# Voorvork.net
KiCad netlist of a schematic drawn in Altium Designer
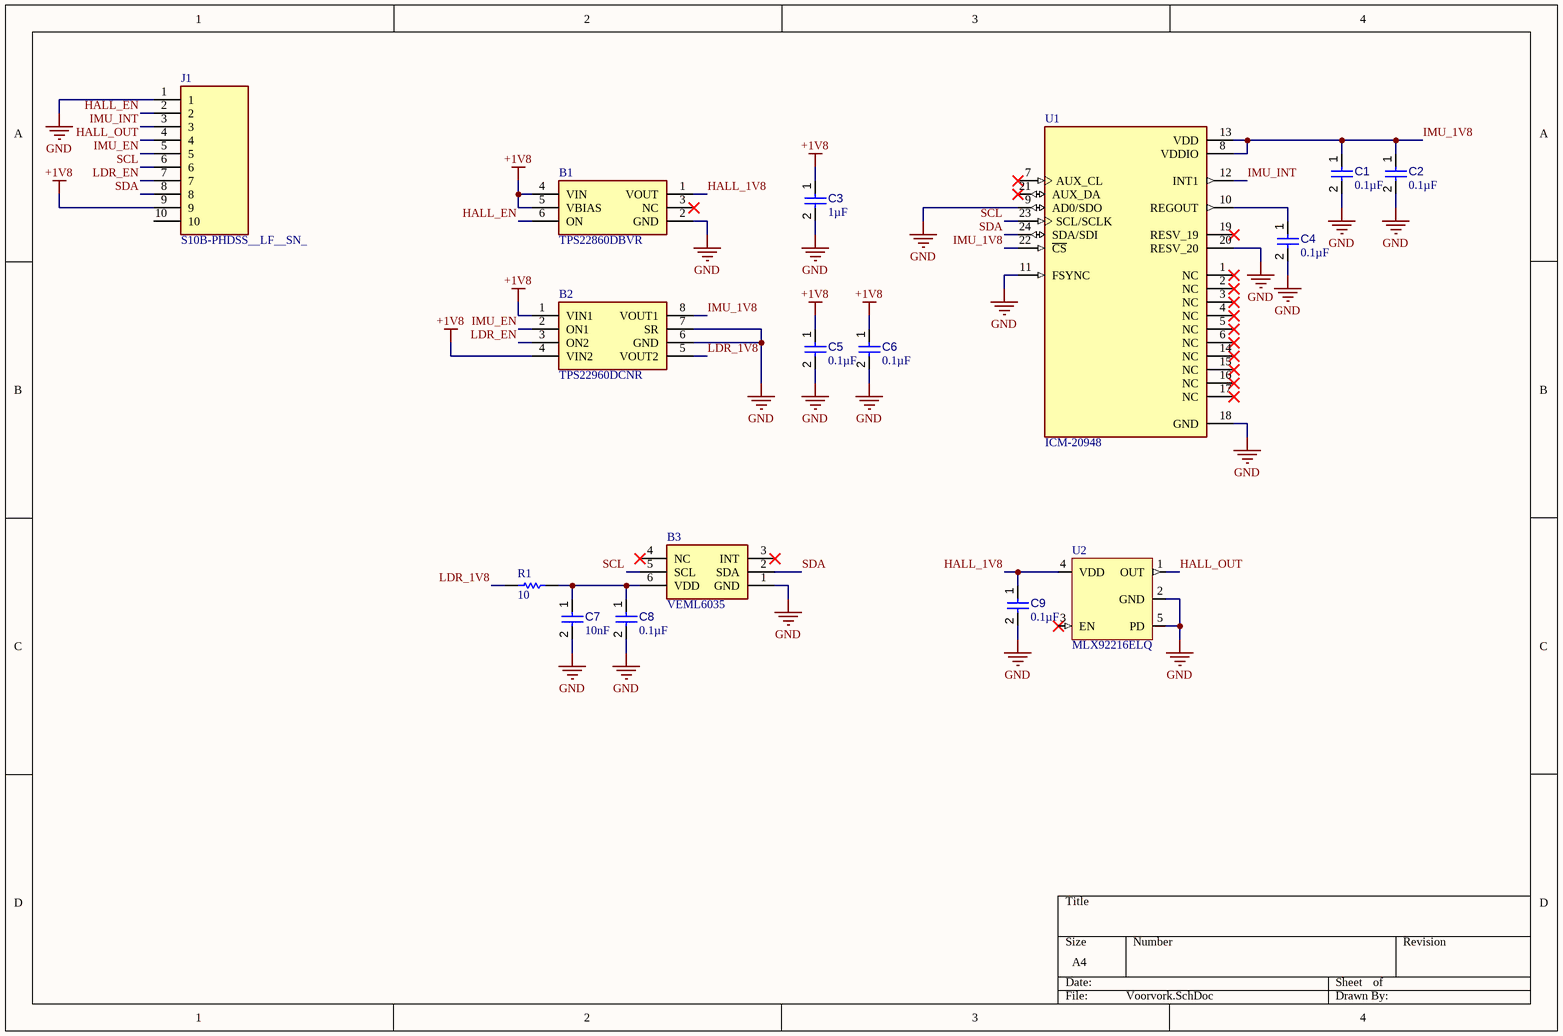
[diagram p0: Voorvork.SchDoc]

(export (version "E")
  (design (tool "Eeschema 10.0.6"))
  (components
    (comp (ref "B1")
      (value "TPS22860DBVR")
      (footprint "SOT95P280X145-6N")
      (description "TPS22860 Ultra-low leakage load switch")
      (fields (field (name "MOUSER PART NUMBER") "595-TPS22860DBVR"))
      (libsource (lib "Integrated_Library1") (part "TPS22860DBVR"))
    )
    (comp (ref "B2")
      (value "TPS22960DCNR")
      (footprint "SOP65P280X145-8N")
      (description "5.5-V, 0.5-A, 435m, 2-channel load switch with quick output discharge")
      (fields (field (name "MOUSER PART NUMBER") "595-TPS22960DCNR"))
      (libsource (lib "Integrated_Library1") (part "TPS22960DCNR"))
    )
    (comp (ref "B3")
      (value "VEML6035")
      (footprint "VEML6035")
      (description "VISHAY - VEML6035 - AMBIENT LIGHT PHOTO SENSOR, I2C, SMD-6")
      (fields (field (name "MOUSER PART NUMBER") "78-VEML6035"))
      (libsource (lib "Integrated_Library1") (part "VEML6035"))
    )
    (comp (ref "C1")
      (value "0.1µF")
      (footprint "CAPC2013X95X50LL10T25")
      (description "Chip Capacitor, 100 nF, +/- 10%, 50 V, 0805 (2012 Metric)")
      (fields (field (name "TOLERANCE") "10%") (field (name "Comment") "Capacitor 100 nF +/-10% 50 V 0805"))
      (libsource (lib "Arne Van der Stede") (part "CAP-NP-2"))
    )
    (comp (ref "C2")
      (value "0.1µF")
      (footprint "CAPC2013X95X50LL10T25")
      (description "Chip Capacitor, 100 nF, +/- 10%, 50 V, 0805 (2012 Metric)")
      (fields (field (name "TOLERANCE") "10%") (field (name "Comment") "Capacitor 100 nF +/-10% 50 V 0805"))
      (libsource (lib "Arne Van der Stede") (part "CAP-NP-2"))
    )
    (comp (ref "C3")
      (value "1µF")
      (footprint "CAPC2013X95X50LL10T25")
      (description "Chip Capacitor, 100 nF, +/- 10%, 50 V, 0805 (2012 Metric)")
      (fields (field (name "TOLERANCE") "10%") (field (name "Comment") "Capacitor 100 nF +/-10% 50 V 0805"))
      (libsource (lib "Arne Van der Stede") (part "CAP-NP-2"))
    )
    (comp (ref "C4")
      (value "0.1µF")
      (footprint "CAPC2013X95X50LL10T25")
      (description "Chip Capacitor, 100 nF, +/- 10%, 50 V, 0805 (2012 Metric)")
      (fields (field (name "TOLERANCE") "10%") (field (name "Comment") "Capacitor 100 nF +/-10% 50 V 0805"))
      (libsource (lib "Arne Van der Stede") (part "CAP-NP-2"))
    )
    (comp (ref "C5")
      (value "0.1µF")
      (footprint "CAPC2013X95X50LL10T25")
      (description "Chip Capacitor, 100 nF, +/- 10%, 50 V, 0805 (2012 Metric)")
      (fields (field (name "TOLERANCE") "10%") (field (name "Comment") "Capacitor 100 nF +/-10% 50 V 0805"))
      (libsource (lib "Arne Van der Stede") (part "CAP-NP-2"))
    )
    (comp (ref "C6")
      (value "0.1µF")
      (footprint "CAPC2013X95X50LL10T25")
      (description "Chip Capacitor, 100 nF, +/- 10%, 50 V, 0805 (2012 Metric)")
      (fields (field (name "TOLERANCE") "10%") (field (name "Comment") "Capacitor 100 nF +/-10% 50 V 0805"))
      (libsource (lib "Arne Van der Stede") (part "CAP-NP-2"))
    )
    (comp (ref "C7")
      (value "10nF")
      (footprint "CAPC2013X95X50LL10T25")
      (description "Chip Capacitor, 100 nF, +/- 10%, 50 V, 0805 (2012 Metric)")
      (fields (field (name "TOLERANCE") "10%") (field (name "Comment") "Capacitor 100 nF +/-10% 50 V 0805"))
      (libsource (lib "Arne Van der Stede") (part "CAP-NP-2"))
    )
    (comp (ref "C8")
      (value "0.1µF")
      (footprint "CAPC2013X95X50LL10T25")
      (description "Chip Capacitor, 100 nF, +/- 10%, 50 V, 0805 (2012 Metric)")
      (fields (field (name "TOLERANCE") "10%") (field (name "Comment") "Capacitor 100 nF +/-10% 50 V 0805"))
      (libsource (lib "Arne Van der Stede") (part "CAP-NP-2"))
    )
    (comp (ref "C9")
      (value "0.1µF")
      (footprint "CAPC2013X95X50LL10T25")
      (description "Chip Capacitor, 100 nF, +/- 10%, 50 V, 0805 (2012 Metric)")
      (fields (field (name "TOLERANCE") "10%") (field (name "Comment") "Capacitor 100 nF +/-10% 50 V 0805"))
      (libsource (lib "Arne Van der Stede") (part "CAP-NP-2"))
    )
    (comp (ref "J1")
      (value "S10B-PHDSS__LF__SN_")
      (footprint "S10BPHDSSLFSN")
      (description "Connector Header Through Hole, Right Angle 10 position 0.079\" (2.00mm)")
      (fields (field (name "MANUFACTURER_PART_NUMBER") "S10B-PHDSS (LF)(SN)"))
      (libsource (lib "Integrated_Library1") (part "S10B-PHDSS__LF__SN_"))
    )
    (comp (ref "R1")
      (value "10")
      (footprint "RESC2013X70X40ML20T20")
      (description "Chip Resistor, 1 KOhm, +/- 1%, 0.125 W, -55 to 155 degC, 0805 (2013 Metric)")
      (fields (field (name "TOLERANCE") "1%") (field (name "POWER") "125mW"))
      (libsource (lib "Arne Van der Stede") (part "RES-2"))
    )
    (comp (ref "U1")
      (value "ICM-20948")
      (footprint "QFN40P300X300X105-24N")
      (description "Accelerometer, Gyroscope, Magnetometer, 9 Axis Sensor I2C, SPI Output")
      (fields (field (name "MF") "TDK InvenSense"))
      (libsource (lib "Arne Van der Stede") (part "ICM-20948"))
    )
    (comp (ref "U2")
      (value "MLX92216ELQ")
      (footprint "DFN-4L")
      (libsource (lib "Integrated_Library1") (part "MLX92216ELQ"))
    )
  )
  (nets
    (net (code "1") (name "+1V8") (class "Default")
      (node (ref "B1") (pin "4") (pinfunction "VIN_4") (pintype "passive"))
      (node (ref "B1") (pin "5") (pinfunction "VBIAS_5") (pintype "passive"))
      (node (ref "B2") (pin "1") (pinfunction "VIN1_1") (pintype "passive"))
      (node (ref "B2") (pin "4") (pinfunction "VIN2_4") (pintype "passive"))
      (node (ref "C3") (pin "1") (pinfunction "1_1") (pintype "passive"))
      (node (ref "C5") (pin "1") (pinfunction "1_1") (pintype "passive"))
      (node (ref "C6") (pin "1") (pinfunction "1_1") (pintype "passive"))
      (node (ref "J1") (pin "9") (pinfunction "9_9") (pintype "passive"))
    )
    (net (code "2") (name "/HALL_1V8") (class "Default")
      (node (ref "B1") (pin "1") (pinfunction "VOUT_1") (pintype "passive"))
      (node (ref "C9") (pin "1") (pinfunction "1_1") (pintype "passive"))
      (node (ref "U2") (pin "4") (pinfunction "VDD_4") (pintype "power_in"))
    )
    (net (code "3") (name "/HALL_EN") (class "Default")
      (node (ref "B1") (pin "6") (pinfunction "ON_6") (pintype "passive"))
      (node (ref "J1") (pin "2") (pinfunction "2_2") (pintype "passive"))
    )
    (net (code "4") (name "/HALL_OUT") (class "Default")
      (node (ref "J1") (pin "4") (pinfunction "4_4") (pintype "passive"))
      (node (ref "U2") (pin "1") (pinfunction "OUT_1") (pintype "output"))
    )
    (net (code "5") (name "/IMU_1V8") (class "Default")
      (node (ref "B2") (pin "8") (pinfunction "VOUT1_8") (pintype "passive"))
      (node (ref "C1") (pin "1") (pinfunction "1_1") (pintype "passive"))
      (node (ref "C2") (pin "1") (pinfunction "1_1") (pintype "passive"))
      (node (ref "U1") (pin "13") (pinfunction "VDD_13") (pintype "power_in"))
      (node (ref "U1") (pin "22") (pinfunction "~{CS}_22") (pintype "input"))
      (node (ref "U1") (pin "8") (pinfunction "VDDIO_8") (pintype "power_in"))
    )
    (net (code "6") (name "/IMU_EN") (class "Default")
      (node (ref "B2") (pin "2") (pinfunction "ON1_2") (pintype "passive"))
      (node (ref "J1") (pin "5") (pinfunction "5_5") (pintype "passive"))
    )
    (net (code "7") (name "/IMU_INT") (class "Default")
      (node (ref "J1") (pin "3") (pinfunction "3_3") (pintype "passive"))
      (node (ref "U1") (pin "12") (pinfunction "INT1_12") (pintype "output"))
    )
    (net (code "8") (name "/LDR_1V8") (class "Default")
      (node (ref "B2") (pin "5") (pinfunction "VOUT2_5") (pintype "passive"))
      (node (ref "R1") (pin "1") (pinfunction "1_1") (pintype "passive"))
    )
    (net (code "9") (name "/LDR_EN") (class "Default")
      (node (ref "B2") (pin "3") (pinfunction "ON2_3") (pintype "passive"))
      (node (ref "J1") (pin "7") (pinfunction "7_7") (pintype "passive"))
    )
    (net (code "10") (name "/SCL") (class "Default")
      (node (ref "B3") (pin "5") (pinfunction "SCL_5") (pintype "passive"))
      (node (ref "J1") (pin "6") (pinfunction "6_6") (pintype "passive"))
      (node (ref "U1") (pin "23") (pinfunction "SCL/SCLK_23") (pintype "input"))
    )
    (net (code "11") (name "/SDA") (class "Default")
      (node (ref "B3") (pin "2") (pinfunction "SDA_2") (pintype "passive"))
      (node (ref "J1") (pin "8") (pinfunction "8_8") (pintype "passive"))
      (node (ref "U1") (pin "24") (pinfunction "SDA/SDI_24") (pintype "bidirectional"))
    )
    (net (code "12") (name "GND") (class "Default")
      (node (ref "B1") (pin "2") (pinfunction "GND_2") (pintype "passive"))
      (node (ref "B2") (pin "6") (pinfunction "GND_6") (pintype "passive"))
      (node (ref "B2") (pin "7") (pinfunction "SR_7") (pintype "passive"))
      (node (ref "B3") (pin "1") (pinfunction "GND_1") (pintype "passive"))
      (node (ref "C1") (pin "2") (pinfunction "2_2") (pintype "passive"))
      (node (ref "C2") (pin "2") (pinfunction "2_2") (pintype "passive"))
      (node (ref "C3") (pin "2") (pinfunction "2_2") (pintype "passive"))
      (node (ref "C4") (pin "2") (pinfunction "2_2") (pintype "passive"))
      (node (ref "C5") (pin "2") (pinfunction "2_2") (pintype "passive"))
      (node (ref "C6") (pin "2") (pinfunction "2_2") (pintype "passive"))
      (node (ref "C7") (pin "2") (pinfunction "2_2") (pintype "passive"))
      (node (ref "C8") (pin "2") (pinfunction "2_2") (pintype "passive"))
      (node (ref "C9") (pin "2") (pinfunction "2_2") (pintype "passive"))
      (node (ref "J1") (pin "1") (pinfunction "1_1") (pintype "passive"))
      (node (ref "U1") (pin "11") (pinfunction "FSYNC_11") (pintype "input"))
      (node (ref "U1") (pin "18") (pinfunction "GND_18") (pintype "power_in"))
      (node (ref "U1") (pin "20") (pinfunction "RESV_20_20") (pintype "passive"))
      (node (ref "U1") (pin "9") (pinfunction "AD0/SDO_9") (pintype "bidirectional"))
      (node (ref "U2") (pin "2") (pinfunction "GND_2") (pintype "passive"))
      (node (ref "U2") (pin "5") (pinfunction "PD_5") (pintype "passive"))
    )
    (net (code "13") (name "Net-(B3-VDD)") (class "Default")
      (node (ref "B3") (pin "6") (pinfunction "VDD_6") (pintype "passive"))
      (node (ref "C7") (pin "1") (pinfunction "1_1") (pintype "passive"))
      (node (ref "C8") (pin "1") (pinfunction "1_1") (pintype "passive"))
      (node (ref "R1") (pin "2") (pinfunction "2_2") (pintype "passive"))
    )
    (net (code "14") (name "Net-(U1-REGOUT)") (class "Default")
      (node (ref "C4") (pin "1") (pinfunction "1_1") (pintype "passive"))
      (node (ref "U1") (pin "10") (pinfunction "REGOUT_10") (pintype "output"))
    )
    (net (code "15") (name "unconnected-(B1-NC-Pad3)") (class "Default")
      (node (ref "B1") (pin "3") (pinfunction "NC_3") (pintype "passive+no_connect"))
    )
    (net (code "16") (name "unconnected-(B3-INT-Pad3)") (class "Default")
      (node (ref "B3") (pin "3") (pinfunction "INT_3") (pintype "passive+no_connect"))
    )
    (net (code "17") (name "unconnected-(B3-NC-Pad4)") (class "Default")
      (node (ref "B3") (pin "4") (pinfunction "NC_4") (pintype "passive+no_connect"))
    )
    (net (code "18") (name "unconnected-(J1-Pad10)") (class "Default")
      (node (ref "J1") (pin "10") (pinfunction "10_10") (pintype "passive"))
    )
    (net (code "19") (name "unconnected-(U1-AUX_CL-Pad7)") (class "Default")
      (node (ref "U1") (pin "7") (pinfunction "AUX_CL_7") (pintype "input+no_connect"))
    )
    (net (code "20") (name "unconnected-(U1-AUX_DA-Pad21)") (class "Default")
      (node (ref "U1") (pin "21") (pinfunction "AUX_DA_21") (pintype "bidirectional+no_connect"))
    )
    (net (code "21") (name "unconnected-(U1-NC-Pad1)") (class "Default")
      (node (ref "U1") (pin "1") (pinfunction "NC_1") (pintype "passive+no_connect"))
    )
    (net (code "22") (name "unconnected-(U1-NC-Pad2)") (class "Default")
      (node (ref "U1") (pin "2") (pinfunction "NC_2") (pintype "passive+no_connect"))
    )
    (net (code "23") (name "unconnected-(U1-NC-Pad3)") (class "Default")
      (node (ref "U1") (pin "3") (pinfunction "NC_3") (pintype "passive+no_connect"))
    )
    (net (code "24") (name "unconnected-(U1-NC-Pad4)") (class "Default")
      (node (ref "U1") (pin "4") (pinfunction "NC_4") (pintype "passive+no_connect"))
    )
    (net (code "25") (name "unconnected-(U1-NC-Pad5)") (class "Default")
      (node (ref "U1") (pin "5") (pinfunction "NC_5") (pintype "passive+no_connect"))
    )
    (net (code "26") (name "unconnected-(U1-NC-Pad6)") (class "Default")
      (node (ref "U1") (pin "6") (pinfunction "NC_6") (pintype "passive+no_connect"))
    )
    (net (code "27") (name "unconnected-(U1-NC-Pad14)") (class "Default")
      (node (ref "U1") (pin "14") (pinfunction "NC_14") (pintype "passive+no_connect"))
    )
    (net (code "28") (name "unconnected-(U1-NC-Pad15)") (class "Default")
      (node (ref "U1") (pin "15") (pinfunction "NC_15") (pintype "passive+no_connect"))
    )
    (net (code "29") (name "unconnected-(U1-NC-Pad16)") (class "Default")
      (node (ref "U1") (pin "16") (pinfunction "NC_16") (pintype "passive+no_connect"))
    )
    (net (code "30") (name "unconnected-(U1-NC-Pad17)") (class "Default")
      (node (ref "U1") (pin "17") (pinfunction "NC_17") (pintype "passive+no_connect"))
    )
    (net (code "31") (name "unconnected-(U1-RESV_19-Pad19)") (class "Default")
      (node (ref "U1") (pin "19") (pinfunction "RESV_19_19") (pintype "passive+no_connect"))
    )
    (net (code "32") (name "unconnected-(U2-EN-Pad3)") (class "Default")
      (node (ref "U2") (pin "3") (pinfunction "EN_3") (pintype "input+no_connect"))
    )
  )
)
